# basic-lipo-manager.net
KiCad netlist of a schematic drawn in EAGLE
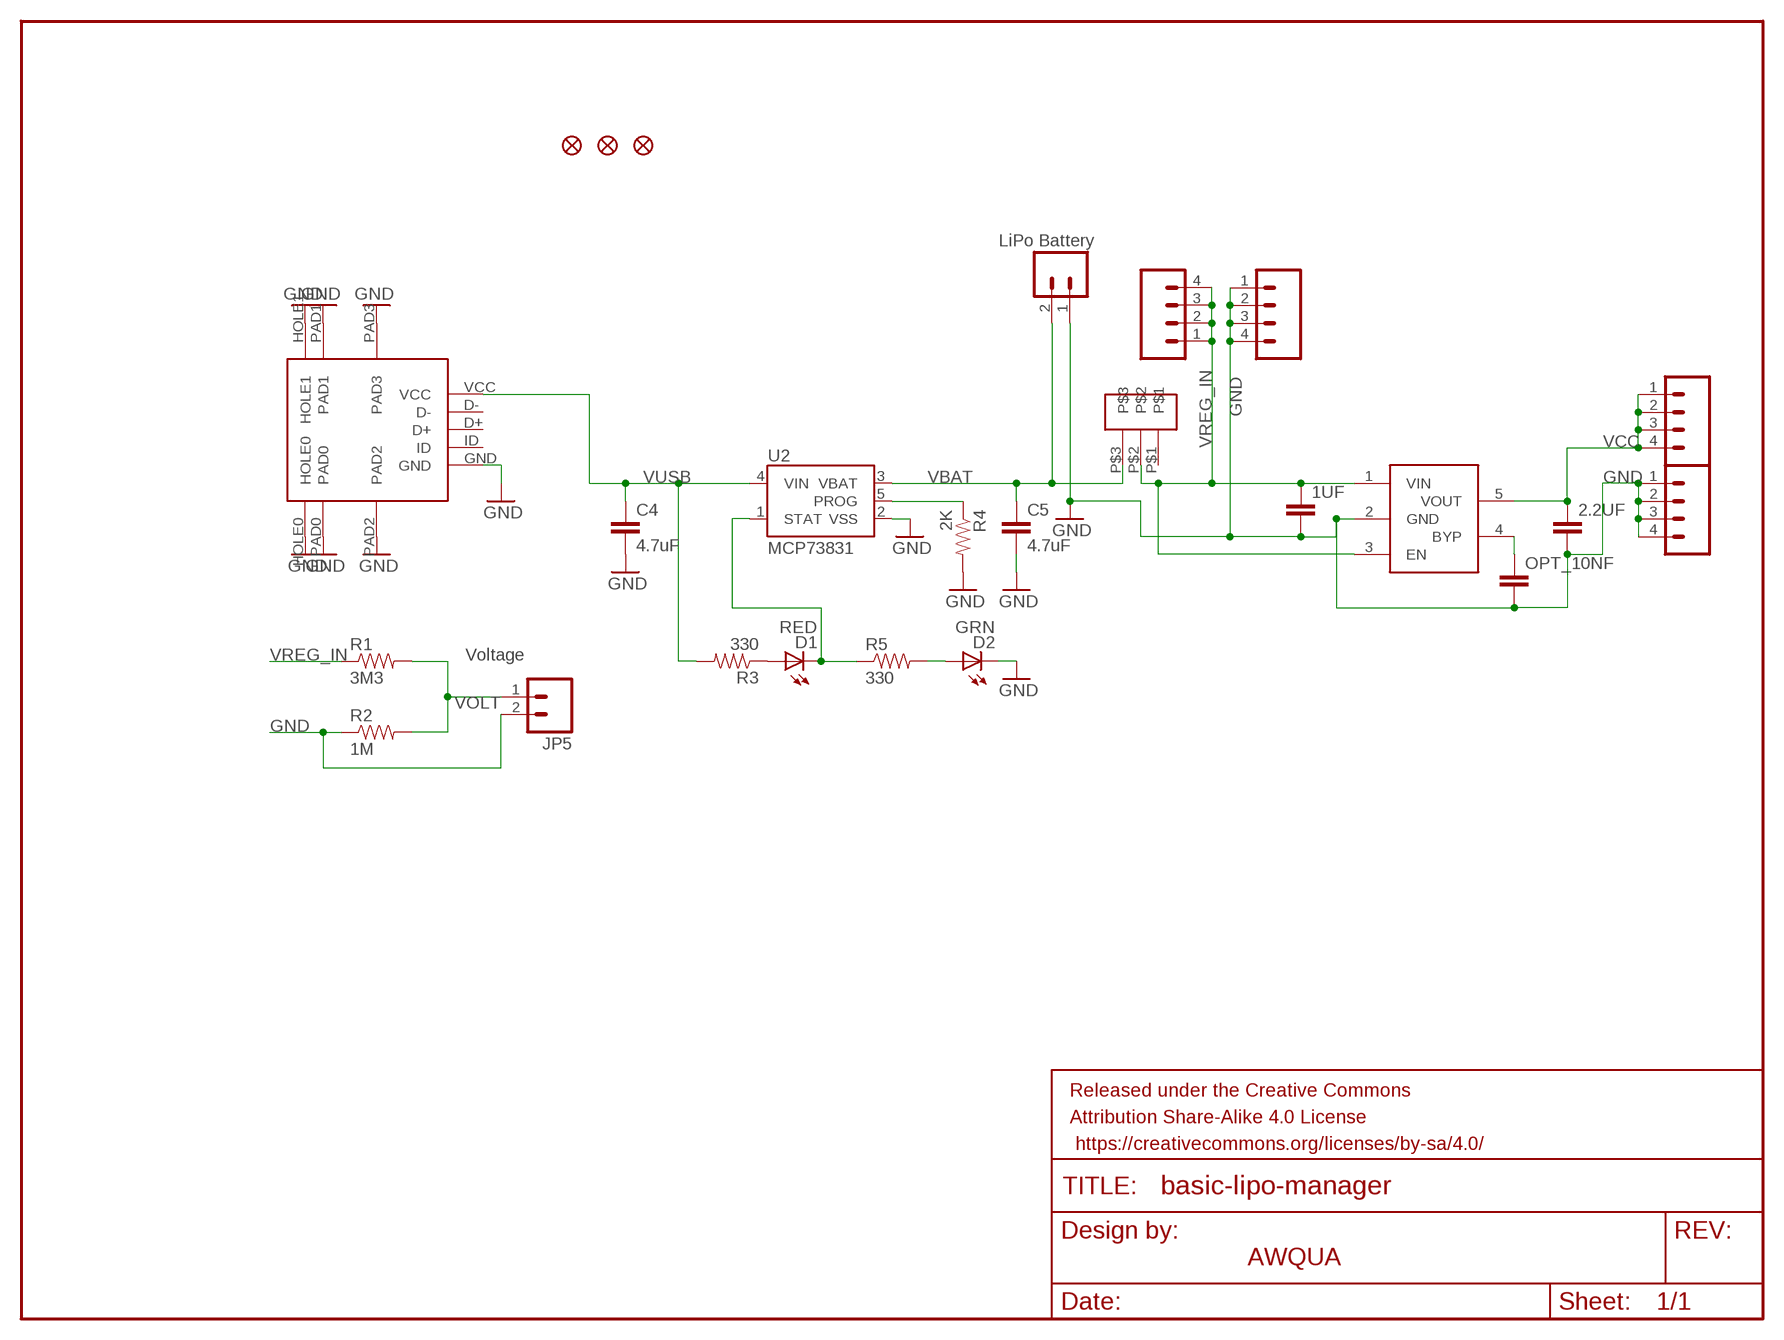
[diagram p0: schematic, sheet 1]

(export (version "E")
  (design (tool "Eeschema 10.0.6"))
  (components
    (comp (ref "1UF")
      (value "CAP0603-CAP")
      (footprint "eagle-import:0603-CAP")
      (libsource (lib "eagle-import") (part "SparkFun-Passives_CAP0603-CAP"))
    )
    (comp (ref "2.2UF")
      (value "CAP0603-CAP")
      (footprint "eagle-import:0603-CAP")
      (libsource (lib "eagle-import") (part "SparkFun-Passives_CAP0603-CAP"))
    )
    (comp (ref "C4")
      (value "4.7uF")
      (footprint "eagle-import:0402-CAP")
      (libsource (lib "eagle-import") (part "CAP0402-CAP"))
    )
    (comp (ref "C5")
      (value "4.7uF")
      (footprint "eagle-import:0402-CAP")
      (libsource (lib "eagle-import") (part "CAP0402-CAP"))
    )
    (comp (ref "D1")
      (value "RED")
      (footprint "eagle-import:LED-0603")
      (libsource (lib "eagle-import") (part "LED0603"))
    )
    (comp (ref "D2")
      (value "GRN")
      (footprint "eagle-import:LED-0603")
      (libsource (lib "eagle-import") (part "LED0603"))
    )
    (comp (ref "FID1")
      (value "FIDUCIAL1X2")
      (footprint "eagle-import:FIDUCIAL-1X2")
      (libsource (lib "eagle-import") (part "FIDUCIAL1X2"))
    )
    (comp (ref "FID2")
      (value "FIDUCIAL1X2")
      (footprint "eagle-import:FIDUCIAL-1X2")
      (libsource (lib "eagle-import") (part "FIDUCIAL1X2"))
    )
    (comp (ref "FID3")
      (value "FIDUCIAL1X2")
      (footprint "eagle-import:FIDUCIAL-1X2")
      (libsource (lib "eagle-import") (part "FIDUCIAL1X2"))
    )
    (comp (ref "FRAME1")
      (value "FRAME-LETTER")
      (footprint "eagle-import:CREATIVE_COMMONS")
      (libsource (lib "eagle-import") (part "FRAME-LETTER"))
    )
    (comp (ref "JP1")
      (value "M04PTH")
      (footprint "eagle-import:1X04")
      (libsource (lib "eagle-import") (part "M04PTH"))
    )
    (comp (ref "JP2")
      (value "M04PTH")
      (footprint "eagle-import:1X04")
      (libsource (lib "eagle-import") (part "M04PTH"))
    )
    (comp (ref "JP3")
      (value "M04PTH")
      (footprint "eagle-import:1X04")
      (libsource (lib "eagle-import") (part "M04PTH"))
    )
    (comp (ref "JP4")
      (value "M04PTH")
      (footprint "eagle-import:1X04")
      (libsource (lib "eagle-import") (part "M04PTH"))
    )
    (comp (ref "JP5")
      (value "M02PTH")
      (footprint "eagle-import:1X02")
      (libsource (lib "eagle-import") (part "SparkFun-Connectors_M02PTH"))
    )
    (comp (ref "JP7")
      (value "LiPo Battery")
      (footprint "eagle-import:JST-2-SMD")
      (libsource (lib "eagle-import") (part "M02-JST-2MM-SMT"))
    )
    (comp (ref "OPT_10NF")
      (value "CAP0603-CAP")
      (footprint "eagle-import:0603-CAP")
      (libsource (lib "eagle-import") (part "SparkFun-Passives_CAP0603-CAP"))
    )
    (comp (ref "R1")
      (value "3M3")
      (footprint "eagle-import:0603-RES")
      (libsource (lib "eagle-import") (part "RESISTOR0603"))
    )
    (comp (ref "R2")
      (value "1M")
      (footprint "eagle-import:0603-RES")
      (libsource (lib "eagle-import") (part "RESISTOR0603"))
    )
    (comp (ref "R3")
      (value "330")
      (footprint "eagle-import:0402-RES")
      (libsource (lib "eagle-import") (part "RESISTOR0402-RES"))
    )
    (comp (ref "R4")
      (value "2K")
      (footprint "eagle-import:0402-RES")
      (libsource (lib "eagle-import") (part "RESISTOR0402-RES"))
    )
    (comp (ref "R5")
      (value "330")
      (footprint "eagle-import:0402-RES")
      (libsource (lib "eagle-import") (part "RESISTOR0402-RES"))
    )
    (comp (ref "U$3")
      (value "USBMICRO-10118193-0001LF")
      (footprint "eagle-import:USBMICRO-10118193-0001LF")
      (libsource (lib "eagle-import") (part "USBMICRO-10118193-0001LF"))
    )
    (comp (ref "U$6")
      (value "LP2985")
      (footprint "eagle-import:LP2985")
      (libsource (lib "eagle-import") (part "LP2985"))
    )
    (comp (ref "U$7")
      (value "OS102-SPDT-SWITCH")
      (footprint "eagle-import:OS102-SPDT-SWITCH")
      (libsource (lib "eagle-import") (part "OS102-SPDT-SWITCH"))
    )
    (comp (ref "U2")
      (value "MCP73831")
      (footprint "eagle-import:SOT23-5")
      (libsource (lib "eagle-import") (part "MCP73831"))
    )
  )
  (nets
    (net (code "1") (name "/VBAT") (class "Default")
      (node (ref "C5") (pin "1") (pinfunction "1_1") (pintype "passive"))
      (node (ref "JP7") (pin "2") (pinfunction "2_2") (pintype "passive"))
      (node (ref "U$7") (pin "P$3") (pinfunction "P$3_P$3") (pintype "bidirectional"))
      (node (ref "U2") (pin "3") (pinfunction "VBAT_3") (pintype "power_in"))
    )
    (net (code "2") (name "/VCC") (class "Default")
      (node (ref "2.2UF") (pin "1") (pinfunction "1_1") (pintype "passive"))
      (node (ref "JP3") (pin "1") (pinfunction "1_1") (pintype "passive"))
      (node (ref "JP3") (pin "2") (pinfunction "2_2") (pintype "passive"))
      (node (ref "JP3") (pin "3") (pinfunction "3_3") (pintype "passive"))
      (node (ref "JP3") (pin "4") (pinfunction "4_4") (pintype "passive"))
      (node (ref "U$6") (pin "5") (pinfunction "VOUT_5") (pintype "bidirectional"))
    )
    (net (code "3") (name "/VOLT") (class "Default")
      (node (ref "JP5") (pin "1") (pinfunction "1_1") (pintype "passive"))
      (node (ref "R1") (pin "2") (pinfunction "2_2") (pintype "passive"))
      (node (ref "R2") (pin "2") (pinfunction "2_2") (pintype "passive"))
    )
    (net (code "4") (name "/VREG_IN") (class "Default")
      (node (ref "1UF") (pin "1") (pinfunction "1_1") (pintype "passive"))
      (node (ref "JP1") (pin "1") (pinfunction "1_1") (pintype "passive"))
      (node (ref "JP1") (pin "2") (pinfunction "2_2") (pintype "passive"))
      (node (ref "JP1") (pin "3") (pinfunction "3_3") (pintype "passive"))
      (node (ref "JP1") (pin "4") (pinfunction "4_4") (pintype "passive"))
      (node (ref "R1") (pin "1") (pinfunction "1_1") (pintype "passive"))
      (node (ref "U$6") (pin "1") (pinfunction "VIN_1") (pintype "bidirectional"))
      (node (ref "U$6") (pin "3") (pinfunction "EN_3") (pintype "bidirectional"))
      (node (ref "U$7") (pin "P$2") (pinfunction "P$2_P$2") (pintype "bidirectional"))
    )
    (net (code "5") (name "/VUSB") (class "Default")
      (node (ref "C4") (pin "1") (pinfunction "1_1") (pintype "passive"))
      (node (ref "R3") (pin "2") (pinfunction "2_2") (pintype "passive"))
      (node (ref "U$3") (pin "VCC") (pinfunction "VCC_VCC") (pintype "bidirectional"))
      (node (ref "U2") (pin "4") (pinfunction "VIN_4") (pintype "power_in"))
    )
    (net (code "6") (name "GND") (class "Default")
      (node (ref "1UF") (pin "2") (pinfunction "2_2") (pintype "passive"))
      (node (ref "2.2UF") (pin "2") (pinfunction "2_2") (pintype "passive"))
      (node (ref "C4") (pin "2") (pinfunction "2_2") (pintype "passive"))
      (node (ref "C5") (pin "2") (pinfunction "2_2") (pintype "passive"))
      (node (ref "D2") (pin "C") (pinfunction "C_C") (pintype "passive"))
      (node (ref "JP2") (pin "1") (pinfunction "1_1") (pintype "passive"))
      (node (ref "JP2") (pin "2") (pinfunction "2_2") (pintype "passive"))
      (node (ref "JP2") (pin "3") (pinfunction "3_3") (pintype "passive"))
      (node (ref "JP2") (pin "4") (pinfunction "4_4") (pintype "passive"))
      (node (ref "JP4") (pin "1") (pinfunction "1_1") (pintype "passive"))
      (node (ref "JP4") (pin "2") (pinfunction "2_2") (pintype "passive"))
      (node (ref "JP4") (pin "3") (pinfunction "3_3") (pintype "passive"))
      (node (ref "JP4") (pin "4") (pinfunction "4_4") (pintype "passive"))
      (node (ref "JP5") (pin "2") (pinfunction "2_2") (pintype "passive"))
      (node (ref "JP7") (pin "1") (pinfunction "1_1") (pintype "passive"))
      (node (ref "OPT_10NF") (pin "2") (pinfunction "2_2") (pintype "passive"))
      (node (ref "R2") (pin "1") (pinfunction "1_1") (pintype "passive"))
      (node (ref "R4") (pin "2") (pinfunction "2_2") (pintype "passive"))
      (node (ref "U$3") (pin "GND") (pinfunction "GND_GND") (pintype "bidirectional"))
      (node (ref "U$3") (pin "HOLE0") (pinfunction "HOLE0_HOLE0") (pintype "bidirectional"))
      (node (ref "U$3") (pin "HOLE1") (pinfunction "HOLE1_HOLE1") (pintype "bidirectional"))
      (node (ref "U$3") (pin "PAD0") (pinfunction "PAD0_PAD0") (pintype "bidirectional"))
      (node (ref "U$3") (pin "PAD1") (pinfunction "PAD1_PAD1") (pintype "bidirectional"))
      (node (ref "U$3") (pin "PAD2") (pinfunction "PAD2_PAD2") (pintype "bidirectional"))
      (node (ref "U$3") (pin "PAD3") (pinfunction "PAD3_PAD3") (pintype "bidirectional"))
      (node (ref "U$6") (pin "2") (pinfunction "GND_2") (pintype "bidirectional"))
      (node (ref "U2") (pin "2") (pinfunction "VSS_2") (pintype "power_in"))
    )
    (net (code "7") (name "Net-(D1-PadA)") (class "Default")
      (node (ref "D1") (pin "A") (pinfunction "A_A") (pintype "passive"))
      (node (ref "R3") (pin "1") (pinfunction "1_1") (pintype "passive"))
    )
    (net (code "8") (name "Net-(D2-PadA)") (class "Default")
      (node (ref "D2") (pin "A") (pinfunction "A_A") (pintype "passive"))
      (node (ref "R5") (pin "2") (pinfunction "2_2") (pintype "passive"))
    )
    (net (code "9") (name "Net-(U$6-BYP)") (class "Default")
      (node (ref "OPT_10NF") (pin "1") (pinfunction "1_1") (pintype "passive"))
      (node (ref "U$6") (pin "4") (pinfunction "BYP_4") (pintype "bidirectional"))
    )
    (net (code "10") (name "Net-(U2-PROG)") (class "Default")
      (node (ref "R4") (pin "1") (pinfunction "1_1") (pintype "passive"))
      (node (ref "U2") (pin "5") (pinfunction "PROG_5") (pintype "input"))
    )
    (net (code "11") (name "Net-(U2-STAT)") (class "Default")
      (node (ref "D1") (pin "C") (pinfunction "C_C") (pintype "passive"))
      (node (ref "R5") (pin "1") (pinfunction "1_1") (pintype "passive"))
      (node (ref "U2") (pin "1") (pinfunction "STAT_1") (pintype "output"))
    )
    (net (code "12") (name "unconnected-(U$3-PadD+)") (class "Default")
      (node (ref "U$3") (pin "D+") (pinfunction "D+_D+") (pintype "bidirectional"))
    )
    (net (code "13") (name "unconnected-(U$3-PadD-)") (class "Default")
      (node (ref "U$3") (pin "D-") (pinfunction "D-_D-") (pintype "bidirectional"))
    )
    (net (code "14") (name "unconnected-(U$3-PadID)") (class "Default")
      (node (ref "U$3") (pin "ID") (pinfunction "ID_ID") (pintype "bidirectional"))
    )
    (net (code "15") (name "unconnected-(U$7-PadP$1)") (class "Default")
      (node (ref "U$7") (pin "P$1") (pinfunction "P$1_P$1") (pintype "bidirectional"))
    )
  )
)
